# LCDTFT_RTP_CONN.net
KiCad netlist of a schematic drawn in Altium Designer
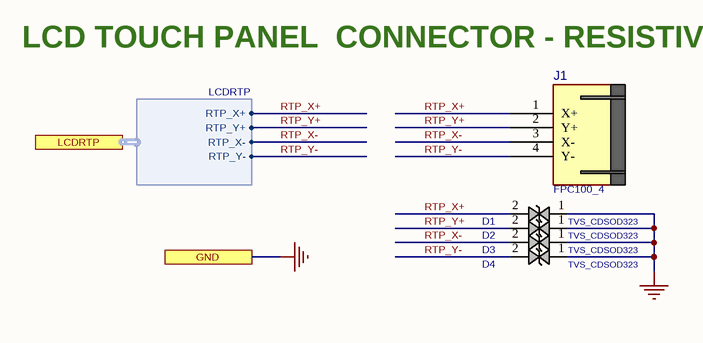
[diagram p0: LCDTFT_RTP_CONN.SchDoc]

(export (version "E")
  (design (tool "Eeschema 10.0.6"))
  (components
    (comp (ref "D1")
      (value "TVS_CDSOD323")
      (footprint "D0805")
      (description "TVS, ESD PROTECT, Bidirectional")
      (fields (field (name "MANF_P#") "CDSOD323-T12C") (field (name "MANF") "Bourns"))
      (libsource (lib "protect_tvs_esd_fuse") (part "TVS_CDSOD323"))
    )
    (comp (ref "D2")
      (value "TVS_CDSOD323")
      (footprint "D0805")
      (description "TVS, ESD PROTECT, Bidirectional")
      (fields (field (name "MANF_P#") "CDSOD323-T12C") (field (name "MANF") "Bourns"))
      (libsource (lib "protect_tvs_esd_fuse") (part "TVS_CDSOD323"))
    )
    (comp (ref "D3")
      (value "TVS_CDSOD323")
      (footprint "D0805")
      (description "TVS, ESD PROTECT, Bidirectional")
      (fields (field (name "MANF_P#") "CDSOD323-T12C") (field (name "MANF") "Bourns"))
      (libsource (lib "protect_tvs_esd_fuse") (part "TVS_CDSOD323"))
    )
    (comp (ref "D4")
      (value "TVS_CDSOD323")
      (footprint "D0805")
      (description "TVS, ESD PROTECT, Bidirectional")
      (fields (field (name "MANF_P#") "CDSOD323-T12C") (field (name "MANF") "Bourns"))
      (libsource (lib "protect_tvs_esd_fuse") (part "TVS_CDSOD323"))
    )
    (comp (ref "J1")
      (value "FPC100_4")
      (footprint "FPC100_4HT")
      (description "LCD Resistive touch, FPC 4pin")
      (libsource (lib "lcdtft") (part "LCD_RTP_FPC4P"))
    )
  )
  (nets
    (net (code "2") (name "/RTP_X+") (class "Default")
      (node (ref "D1") (pin "2") (pinfunction "2_2") (pintype "passive"))
      (node (ref "J1") (pin "1") (pinfunction "X+_1") (pintype "passive"))
    )
    (net (code "3") (name "/RTP_X-") (class "Default")
      (node (ref "D3") (pin "2") (pinfunction "2_2") (pintype "passive"))
      (node (ref "J1") (pin "3") (pinfunction "X-_3") (pintype "passive"))
    )
    (net (code "4") (name "/RTP_Y+") (class "Default")
      (node (ref "D2") (pin "2") (pinfunction "2_2") (pintype "passive"))
      (node (ref "J1") (pin "2") (pinfunction "Y+_2") (pintype "passive"))
    )
    (net (code "5") (name "/RTP_Y-") (class "Default")
      (node (ref "D4") (pin "2") (pinfunction "2_2") (pintype "passive"))
      (node (ref "J1") (pin "4") (pinfunction "Y-_4") (pintype "passive"))
    )
    (net (code "7") (name "GND") (class "Default")
      (node (ref "D1") (pin "1") (pinfunction "1_1") (pintype "passive"))
      (node (ref "D2") (pin "1") (pinfunction "1_1") (pintype "passive"))
      (node (ref "D3") (pin "1") (pinfunction "1_1") (pintype "passive"))
      (node (ref "D4") (pin "1") (pinfunction "1_1") (pintype "passive"))
    )
  )
)
